# BDVLS_0V1.net
KiCad netlist of a schematic drawn in EAGLE
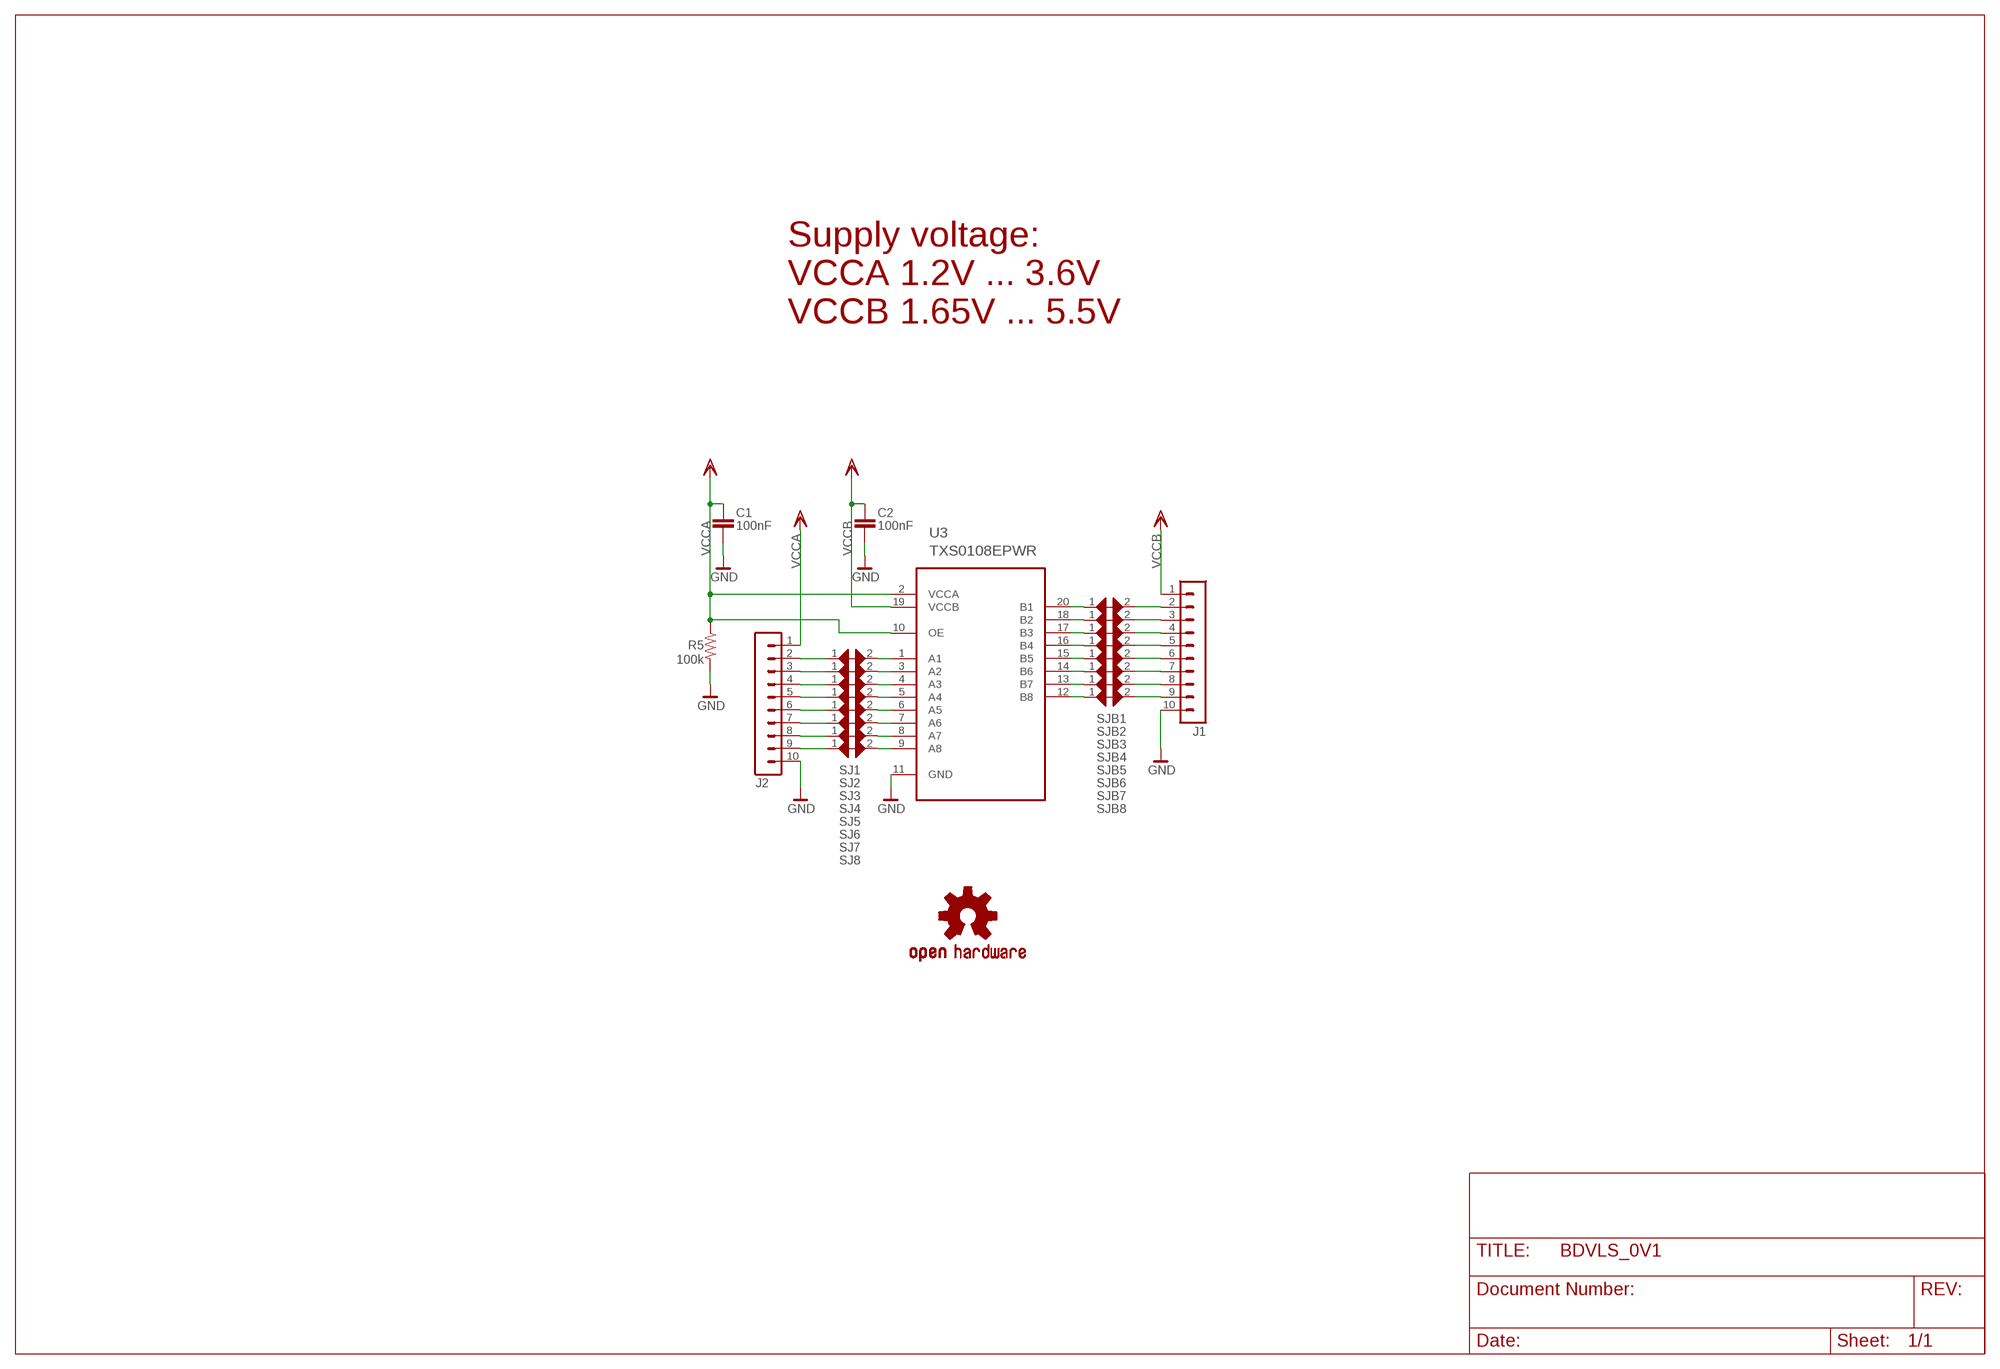
[diagram p0: schematic, sheet 1]

(export (version "E")
  (design (tool "Eeschema 10.0.6"))
  (components
    (comp (ref "C1")
      (value "100nF")
      (footprint "eagle-import:0603")
      (libsource (lib "eagle-import") (part "CAP-SMD0603"))
    )
    (comp (ref "C2")
      (value "100nF")
      (footprint "eagle-import:0603")
      (libsource (lib "eagle-import") (part "CAP-SMD0603"))
    )
    (comp (ref "J1")
      (value "PIN10S")
      (footprint "eagle-import:PIN10S")
      (libsource (lib "eagle-import") (part "PIN10S"))
    )
    (comp (ref "J2")
      (value "PIN10S")
      (footprint "eagle-import:PIN10S")
      (libsource (lib "eagle-import") (part "PIN10S"))
    )
    (comp (ref "R5")
      (value "100k")
      (footprint "eagle-import:R0402")
      (libsource (lib "eagle-import") (part "R-US_R0402"))
    )
    (comp (ref "SJ1")
      (value "printed")
      (footprint "eagle-import:JUMPER_SMD_MICRO_SHORT")
      (libsource (lib "eagle-import") (part "JUMPER_SMD_MICRO_SHORT"))
    )
    (comp (ref "SJ2")
      (value "printed")
      (footprint "eagle-import:JUMPER_SMD_MICRO_SHORT")
      (libsource (lib "eagle-import") (part "JUMPER_SMD_MICRO_SHORT"))
    )
    (comp (ref "SJ3")
      (value "printed")
      (footprint "eagle-import:JUMPER_SMD_MICRO_SHORT")
      (libsource (lib "eagle-import") (part "JUMPER_SMD_MICRO_SHORT"))
    )
    (comp (ref "SJ4")
      (value "printed")
      (footprint "eagle-import:JUMPER_SMD_MICRO_SHORT")
      (libsource (lib "eagle-import") (part "JUMPER_SMD_MICRO_SHORT"))
    )
    (comp (ref "SJ5")
      (value "printed")
      (footprint "eagle-import:JUMPER_SMD_MICRO_SHORT")
      (libsource (lib "eagle-import") (part "JUMPER_SMD_MICRO_SHORT"))
    )
    (comp (ref "SJ6")
      (value "printed")
      (footprint "eagle-import:JUMPER_SMD_MICRO_SHORT")
      (libsource (lib "eagle-import") (part "JUMPER_SMD_MICRO_SHORT"))
    )
    (comp (ref "SJ7")
      (value "printed")
      (footprint "eagle-import:JUMPER_SMD_MICRO_SHORT")
      (libsource (lib "eagle-import") (part "JUMPER_SMD_MICRO_SHORT"))
    )
    (comp (ref "SJ8")
      (value "printed")
      (footprint "eagle-import:JUMPER_SMD_MICRO_SHORT")
      (libsource (lib "eagle-import") (part "JUMPER_SMD_MICRO_SHORT"))
    )
    (comp (ref "SJB1")
      (value "printed")
      (footprint "eagle-import:JUMPER_SMD_MICRO_SHORT")
      (libsource (lib "eagle-import") (part "JUMPER_SMD_MICRO_SHORT"))
    )
    (comp (ref "SJB2")
      (value "printed")
      (footprint "eagle-import:JUMPER_SMD_MICRO_SHORT")
      (libsource (lib "eagle-import") (part "JUMPER_SMD_MICRO_SHORT"))
    )
    (comp (ref "SJB3")
      (value "printed")
      (footprint "eagle-import:JUMPER_SMD_MICRO_SHORT")
      (libsource (lib "eagle-import") (part "JUMPER_SMD_MICRO_SHORT"))
    )
    (comp (ref "SJB4")
      (value "printed")
      (footprint "eagle-import:JUMPER_SMD_MICRO_SHORT")
      (libsource (lib "eagle-import") (part "JUMPER_SMD_MICRO_SHORT"))
    )
    (comp (ref "SJB5")
      (value "printed")
      (footprint "eagle-import:JUMPER_SMD_MICRO_SHORT")
      (libsource (lib "eagle-import") (part "JUMPER_SMD_MICRO_SHORT"))
    )
    (comp (ref "SJB6")
      (value "printed")
      (footprint "eagle-import:JUMPER_SMD_MICRO_SHORT")
      (libsource (lib "eagle-import") (part "JUMPER_SMD_MICRO_SHORT"))
    )
    (comp (ref "SJB7")
      (value "printed")
      (footprint "eagle-import:JUMPER_SMD_MICRO_SHORT")
      (libsource (lib "eagle-import") (part "JUMPER_SMD_MICRO_SHORT"))
    )
    (comp (ref "SJB8")
      (value "printed")
      (footprint "eagle-import:JUMPER_SMD_MICRO_SHORT")
      (libsource (lib "eagle-import") (part "JUMPER_SMD_MICRO_SHORT"))
    )
    (comp (ref "U$11")
      (value "OSHW-LOGOM")
      (footprint "eagle-import:OSHW-LOGO-M")
      (libsource (lib "eagle-import") (part "OSHW-LOGOM"))
    )
    (comp (ref "U3")
      (value "TXS0108EPWR")
      (footprint "eagle-import:SOP65P640X120-20N")
      (libsource (lib "eagle-import") (part "TXB0108PWR"))
    )
  )
  (nets
    (net (code "1") (name "GND") (class "Default")
      (node (ref "C1") (pin "1") (pinfunction "1_1") (pintype "passive"))
      (node (ref "C2") (pin "1") (pinfunction "1_1") (pintype "passive"))
      (node (ref "J1") (pin "10") (pinfunction "10_10") (pintype "passive"))
      (node (ref "J2") (pin "10") (pinfunction "10_10") (pintype "passive"))
      (node (ref "R5") (pin "2") (pinfunction "2_2") (pintype "passive"))
      (node (ref "U3") (pin "11") (pinfunction "GND_11") (pintype "passive"))
    )
    (net (code "2") (name "Net-(J1-Pad2)") (class "Default")
      (node (ref "J1") (pin "2") (pinfunction "2_2") (pintype "passive"))
      (node (ref "SJB1") (pin "2") (pinfunction "2_2") (pintype "passive"))
    )
    (net (code "3") (name "Net-(J1-Pad3)") (class "Default")
      (node (ref "J1") (pin "3") (pinfunction "3_3") (pintype "passive"))
      (node (ref "SJB2") (pin "2") (pinfunction "2_2") (pintype "passive"))
    )
    (net (code "4") (name "Net-(J1-Pad4)") (class "Default")
      (node (ref "J1") (pin "4") (pinfunction "4_4") (pintype "passive"))
      (node (ref "SJB3") (pin "2") (pinfunction "2_2") (pintype "passive"))
    )
    (net (code "5") (name "Net-(J1-Pad5)") (class "Default")
      (node (ref "J1") (pin "5") (pinfunction "5_5") (pintype "passive"))
      (node (ref "SJB4") (pin "2") (pinfunction "2_2") (pintype "passive"))
    )
    (net (code "6") (name "Net-(J1-Pad6)") (class "Default")
      (node (ref "J1") (pin "6") (pinfunction "6_6") (pintype "passive"))
      (node (ref "SJB5") (pin "2") (pinfunction "2_2") (pintype "passive"))
    )
    (net (code "7") (name "Net-(J1-Pad7)") (class "Default")
      (node (ref "J1") (pin "7") (pinfunction "7_7") (pintype "passive"))
      (node (ref "SJB6") (pin "2") (pinfunction "2_2") (pintype "passive"))
    )
    (net (code "8") (name "Net-(J1-Pad8)") (class "Default")
      (node (ref "J1") (pin "8") (pinfunction "8_8") (pintype "passive"))
      (node (ref "SJB7") (pin "2") (pinfunction "2_2") (pintype "passive"))
    )
    (net (code "9") (name "Net-(J1-Pad9)") (class "Default")
      (node (ref "J1") (pin "9") (pinfunction "9_9") (pintype "passive"))
      (node (ref "SJB8") (pin "2") (pinfunction "2_2") (pintype "passive"))
    )
    (net (code "10") (name "Net-(J2-Pad2)") (class "Default")
      (node (ref "J2") (pin "2") (pinfunction "2_2") (pintype "passive"))
      (node (ref "SJ1") (pin "1") (pinfunction "1_1") (pintype "passive"))
    )
    (net (code "11") (name "Net-(J2-Pad3)") (class "Default")
      (node (ref "J2") (pin "3") (pinfunction "3_3") (pintype "passive"))
      (node (ref "SJ2") (pin "1") (pinfunction "1_1") (pintype "passive"))
    )
    (net (code "12") (name "Net-(J2-Pad4)") (class "Default")
      (node (ref "J2") (pin "4") (pinfunction "4_4") (pintype "passive"))
      (node (ref "SJ3") (pin "1") (pinfunction "1_1") (pintype "passive"))
    )
    (net (code "13") (name "Net-(J2-Pad5)") (class "Default")
      (node (ref "J2") (pin "5") (pinfunction "5_5") (pintype "passive"))
      (node (ref "SJ4") (pin "1") (pinfunction "1_1") (pintype "passive"))
    )
    (net (code "14") (name "Net-(J2-Pad6)") (class "Default")
      (node (ref "J2") (pin "6") (pinfunction "6_6") (pintype "passive"))
      (node (ref "SJ5") (pin "1") (pinfunction "1_1") (pintype "passive"))
    )
    (net (code "15") (name "Net-(J2-Pad7)") (class "Default")
      (node (ref "J2") (pin "7") (pinfunction "7_7") (pintype "passive"))
      (node (ref "SJ6") (pin "1") (pinfunction "1_1") (pintype "passive"))
    )
    (net (code "16") (name "Net-(J2-Pad8)") (class "Default")
      (node (ref "J2") (pin "8") (pinfunction "8_8") (pintype "passive"))
      (node (ref "SJ7") (pin "1") (pinfunction "1_1") (pintype "passive"))
    )
    (net (code "17") (name "Net-(J2-Pad9)") (class "Default")
      (node (ref "J2") (pin "9") (pinfunction "9_9") (pintype "passive"))
      (node (ref "SJ8") (pin "1") (pinfunction "1_1") (pintype "passive"))
    )
    (net (code "18") (name "Net-(U3-A1)") (class "Default")
      (node (ref "SJ1") (pin "2") (pinfunction "2_2") (pintype "passive"))
      (node (ref "U3") (pin "1") (pinfunction "A1_1") (pintype "bidirectional"))
    )
    (net (code "19") (name "Net-(U3-A2)") (class "Default")
      (node (ref "SJ2") (pin "2") (pinfunction "2_2") (pintype "passive"))
      (node (ref "U3") (pin "3") (pinfunction "A2_3") (pintype "bidirectional"))
    )
    (net (code "20") (name "Net-(U3-A3)") (class "Default")
      (node (ref "SJ3") (pin "2") (pinfunction "2_2") (pintype "passive"))
      (node (ref "U3") (pin "4") (pinfunction "A3_4") (pintype "bidirectional"))
    )
    (net (code "21") (name "Net-(U3-A4)") (class "Default")
      (node (ref "SJ4") (pin "2") (pinfunction "2_2") (pintype "passive"))
      (node (ref "U3") (pin "5") (pinfunction "A4_5") (pintype "bidirectional"))
    )
    (net (code "22") (name "Net-(U3-A5)") (class "Default")
      (node (ref "SJ5") (pin "2") (pinfunction "2_2") (pintype "passive"))
      (node (ref "U3") (pin "6") (pinfunction "A5_6") (pintype "bidirectional"))
    )
    (net (code "23") (name "Net-(U3-A6)") (class "Default")
      (node (ref "SJ6") (pin "2") (pinfunction "2_2") (pintype "passive"))
      (node (ref "U3") (pin "7") (pinfunction "A6_7") (pintype "bidirectional"))
    )
    (net (code "24") (name "Net-(U3-A7)") (class "Default")
      (node (ref "SJ7") (pin "2") (pinfunction "2_2") (pintype "passive"))
      (node (ref "U3") (pin "8") (pinfunction "A7_8") (pintype "bidirectional"))
    )
    (net (code "25") (name "Net-(U3-A8)") (class "Default")
      (node (ref "SJ8") (pin "2") (pinfunction "2_2") (pintype "passive"))
      (node (ref "U3") (pin "9") (pinfunction "A8_9") (pintype "bidirectional"))
    )
    (net (code "26") (name "Net-(U3-B1)") (class "Default")
      (node (ref "SJB1") (pin "1") (pinfunction "1_1") (pintype "passive"))
      (node (ref "U3") (pin "20") (pinfunction "B1_20") (pintype "bidirectional"))
    )
    (net (code "27") (name "Net-(U3-B2)") (class "Default")
      (node (ref "SJB2") (pin "1") (pinfunction "1_1") (pintype "passive"))
      (node (ref "U3") (pin "18") (pinfunction "B2_18") (pintype "bidirectional"))
    )
    (net (code "28") (name "Net-(U3-B3)") (class "Default")
      (node (ref "SJB3") (pin "1") (pinfunction "1_1") (pintype "passive"))
      (node (ref "U3") (pin "17") (pinfunction "B3_17") (pintype "bidirectional"))
    )
    (net (code "29") (name "Net-(U3-B4)") (class "Default")
      (node (ref "SJB4") (pin "1") (pinfunction "1_1") (pintype "passive"))
      (node (ref "U3") (pin "16") (pinfunction "B4_16") (pintype "bidirectional"))
    )
    (net (code "30") (name "Net-(U3-B5)") (class "Default")
      (node (ref "SJB5") (pin "1") (pinfunction "1_1") (pintype "passive"))
      (node (ref "U3") (pin "15") (pinfunction "B5_15") (pintype "bidirectional"))
    )
    (net (code "31") (name "Net-(U3-B6)") (class "Default")
      (node (ref "SJB6") (pin "1") (pinfunction "1_1") (pintype "passive"))
      (node (ref "U3") (pin "14") (pinfunction "B6_14") (pintype "bidirectional"))
    )
    (net (code "32") (name "Net-(U3-B7)") (class "Default")
      (node (ref "SJB7") (pin "1") (pinfunction "1_1") (pintype "passive"))
      (node (ref "U3") (pin "13") (pinfunction "B7_13") (pintype "bidirectional"))
    )
    (net (code "33") (name "Net-(U3-B8)") (class "Default")
      (node (ref "SJB8") (pin "1") (pinfunction "1_1") (pintype "passive"))
      (node (ref "U3") (pin "12") (pinfunction "B8_12") (pintype "bidirectional"))
    )
    (net (code "34") (name "VCCA") (class "Default")
      (node (ref "C1") (pin "2") (pinfunction "2_2") (pintype "passive"))
      (node (ref "J2") (pin "1") (pinfunction "1_1") (pintype "passive"))
      (node (ref "R5") (pin "1") (pinfunction "1_1") (pintype "passive"))
      (node (ref "U3") (pin "10") (pinfunction "OE_10") (pintype "input"))
      (node (ref "U3") (pin "2") (pinfunction "VCCA_2") (pintype "power_in"))
    )
    (net (code "35") (name "VCCB") (class "Default")
      (node (ref "C2") (pin "2") (pinfunction "2_2") (pintype "passive"))
      (node (ref "J1") (pin "1") (pinfunction "1_1") (pintype "passive"))
      (node (ref "U3") (pin "19") (pinfunction "VCCB_19") (pintype "power_in"))
    )
  )
)
